# suicide-switch-circuit-with-usb-battery-.net
KiCad netlist of a schematic drawn in Altium Designer
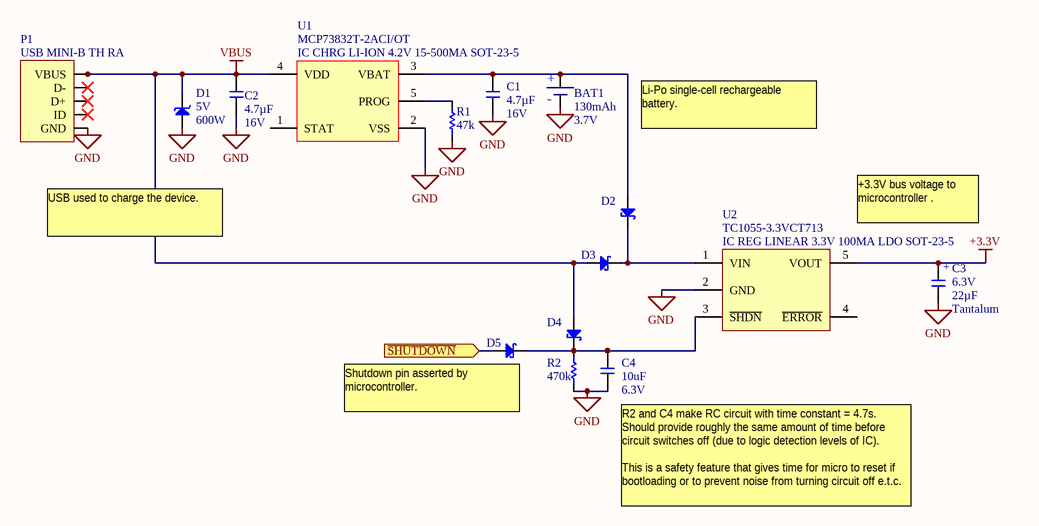
[diagram p0: suicide-switch-circuit-with-usb-battery-charger.SchDoc]

(export (version "E")
  (design (tool "Eeschema 10.0.6"))
  (components
    (comp (ref "BAT1")
      (value "BAT")
      (description "BATT LI-PO 1CELL")
      (fields (field (name "CAPACITY") "130mAh") (field (name "VOLTAGE") "3.7V"))
      (libsource (lib "Generic Components") (part "BATT"))
    )
    (comp (ref "C1")
      (value "EMK212BJ475KG-T")
      (footprint "Generic Footprints:CAP-N-1608[0603]")
      (description "CAP CER 4.7UF 16V 10% X5R 0805")
      (fields
        (field (name "MANUFACTURER") "Taiyo Yuden")
        (field (name "CAPACITANCE") "4.7µF")
        (field (name "VOLTAGE - RATED") "16V")
      )
      (libsource (lib "Specific Components") (part "EMK212BJ475KG-T"))
    )
    (comp (ref "C2")
      (value "EMK212BJ475KG-T")
      (footprint "Generic Footprints:CAP-N-1608[0603]")
      (description "CAP CER 4.7UF 16V 10% X5R 0805")
      (fields
        (field (name "MANUFACTURER") "Taiyo Yuden")
        (field (name "CAPACITANCE") "4.7µF")
        (field (name "VOLTAGE - RATED") "16V")
      )
      (libsource (lib "Specific Components") (part "EMK212BJ475KG-T"))
    )
    (comp (ref "C3")
      (value "TAJA226K006RNJ")
      (footprint "Generic Footprints:CAP TAN 3216[1206]")
      (description "CAP TANT 22UF 6.3V 10% 1206")
      (fields
        (field (name "MANUFACTURER") "AVX Corporation")
        (field (name "VOLTAGE - RATED") "6.3V")
        (field (name "CAPACITANCE") "22µF")
        (field (name "TYPE") "Tantalum")
      )
      (libsource (lib "Specific Components") (part "TAJA226K006RNJ"))
    )
    (comp (ref "C4")
      (value "GRM31CR60J107ME39L")
      (footprint "Generic Footprints:CAP-N-3216[1206]")
      (description "CAP CER 1206 100uF 6.3V X5R 20%")
      (fields (field (name "CAPACITANCE") "10uF") (field (name "VOLTAGE - RATED") "6.3V"))
      (libsource (lib "Specific Components") (part "GRM31CR60J107ME39L"))
    )
    (comp (ref "D1")
      (value "SMA6J5.0A-TR")
      (footprint "Generic Footprints:SMA (DO-214AC)")
      (description "TRANSIL 600W 5.0V UNIDIRECT SMA")
      (fields
        (field (name "MANUFACTURER") "STMicroelectronics")
        (field (name "VOLTAGE - REVERSE STANDOFF (TYP)") "5V")
        (field (name "POWER (WATTS)") "600W")
      )
      (libsource (lib "Specific Components") (part "SMA6J5.0A-TR"))
    )
    (comp (ref "D2")
      (value "CDBU0130L")
      (footprint "DIODE-N-1608[0603]")
      (description "DIODE SCHOTTKY 100MA 30V 0603")
      (fields (field (name "MANUFACTURER") "Comchip Technology"))
      (libsource (lib "Specific Components") (part "CDBU0130L"))
    )
    (comp (ref "D3")
      (value "CDBU0130L")
      (footprint "DIODE-N-1608[0603]")
      (description "DIODE SCHOTTKY 100MA 30V 0603")
      (fields (field (name "MANUFACTURER") "Comchip Technology"))
      (libsource (lib "Specific Components") (part "CDBU0130L"))
    )
    (comp (ref "D4")
      (value "CDBU0130L")
      (footprint "DIODE-N-1608[0603]")
      (description "DIODE SCHOTTKY 100MA 30V 0603")
      (fields (field (name "MANUFACTURER") "Comchip Technology"))
      (libsource (lib "Specific Components") (part "CDBU0130L"))
    )
    (comp (ref "D5")
      (value "CDBU0130L")
      (footprint "DIODE-N-1608[0603]")
      (description "DIODE SCHOTTKY 100MA 30V 0603")
      (fields (field (name "MANUFACTURER") "Comchip Technology"))
      (libsource (lib "Specific Components") (part "CDBU0130L"))
    )
    (comp (ref "P1")
      (value "USB MINI-B TH RA")
      (footprint "Connector Footprints:USB MINI-B TH RA")
      (description "USB MINI-B TH RA")
      (fields
        (field (name "MANUFACTURER") "Molex Inc")
        (field (name "MANUFACTURER PART NUMBER") "0548190519")
      )
      (libsource (lib "Connector Components") (part "USB MINI-B TH RA"))
    )
    (comp (ref "R1")
      (value "RC0603FR-0747KL")
      (footprint "Generic Footprints:RES-N-1608[0603]")
      (description "RES 47.0K OHM 1/10W 1% 0603 SMD")
      (fields (field (name "MANUFACTURER") "Yageo") (field (name "RESISTANCE (OHMS)") "47k"))
      (libsource (lib "Specific Components") (part "RC0603FR-0747KL"))
    )
    (comp (ref "R2")
      (value "RC0603FR-0747KL")
      (footprint "Generic Footprints:RES-N-1608[0603]")
      (description "RES 47.0K OHM 1/10W 1% 0603 SMD")
      (fields (field (name "MANUFACTURER") "Yageo") (field (name "RESISTANCE (OHMS)") "470k"))
      (libsource (lib "Specific Components") (part "RC0603FR-0747KL"))
    )
    (comp (ref "U1")
      (value "~")
      (footprint "Generic Footprints:SOT-23-5")
      (description "IC CHRG LI-ION 4.2V 15-500MA SOT-23-5")
      (fields
        (field (name "MANUFACTURER") "Microchip Technology")
        (field (name "MANUFACTURER PART NUMBER") "MCP73832T-2ACI/OT")
      )
      (libsource (lib "Specific Components") (part "MCP73832T-2ACI/OT"))
    )
    (comp (ref "U2")
      (value "TC1055-3.3VCT713")
      (footprint "Generic Footprints:SOT-23-5")
      (description "IC REG LINEAR 3.3V 100MA LDO SOT-23-5")
      (fields
        (field (name "MANUFACTURER") "Microchip Technology")
        (field (name "MANUFACTURER PART NUMBER") "TC1055-3.3VCT713")
      )
      (libsource (lib "Specific Components") (part "TC1055-3.3VCT713"))
    )
  )
  (nets
    (net (code "1") (name "+3.3V") (class "Default")
      (node (ref "C3") (pin "1") (pinfunction "1_1") (pintype "passive"))
      (node (ref "U2") (pin "5") (pinfunction "VOUT_5") (pintype "passive"))
    )
    (net (code "2") (name "/SHUTDOWN") (class "Default")
      (node (ref "D5") (pin "1") (pinfunction "A_1") (pintype "passive"))
    )
    (net (code "3") (name "GND") (class "Default")
      (node (ref "BAT1") (pin "2") (pinfunction "-_2") (pintype "passive"))
      (node (ref "C1") (pin "1") (pinfunction "1_1") (pintype "passive"))
      (node (ref "C2") (pin "1") (pinfunction "1_1") (pintype "passive"))
      (node (ref "C3") (pin "2") (pinfunction "2_2") (pintype "passive"))
      (node (ref "C4") (pin "1") (pinfunction "1_1") (pintype "passive"))
      (node (ref "D1") (pin "1") (pinfunction "A_1") (pintype "passive"))
      (node (ref "P1") (pin "5") (pinfunction "GND_5") (pintype "passive"))
      (node (ref "R1") (pin "1") (pinfunction "1_1") (pintype "passive"))
      (node (ref "R2") (pin "1") (pinfunction "1_1") (pintype "passive"))
      (node (ref "U1") (pin "2") (pinfunction "VSS_2") (pintype "passive"))
      (node (ref "U2") (pin "2") (pinfunction "GND_2") (pintype "passive"))
    )
    (net (code "4") (name "Net-(BAT1-+)") (class "Default")
      (node (ref "BAT1") (pin "1") (pinfunction "+_1") (pintype "passive"))
      (node (ref "C1") (pin "2") (pinfunction "2_2") (pintype "passive"))
      (node (ref "D2") (pin "1") (pinfunction "A_1") (pintype "passive"))
      (node (ref "U1") (pin "3") (pinfunction "VBAT_3") (pintype "passive"))
    )
    (net (code "5") (name "Net-(D2-K)") (class "Default")
      (node (ref "D2") (pin "2") (pinfunction "K_2") (pintype "passive"))
      (node (ref "D3") (pin "2") (pinfunction "K_2") (pintype "passive"))
      (node (ref "U2") (pin "1") (pinfunction "VIN_1") (pintype "passive"))
    )
    (net (code "6") (name "Net-(D4-K)") (class "Default")
      (node (ref "C4") (pin "2") (pinfunction "2_2") (pintype "passive"))
      (node (ref "D4") (pin "2") (pinfunction "K_2") (pintype "passive"))
      (node (ref "D5") (pin "2") (pinfunction "K_2") (pintype "passive"))
      (node (ref "R2") (pin "2") (pinfunction "2_2") (pintype "passive"))
      (node (ref "U2") (pin "3") (pinfunction "SHDN_3") (pintype "passive"))
    )
    (net (code "7") (name "Net-(U1-PROG)") (class "Default")
      (node (ref "R1") (pin "2") (pinfunction "2_2") (pintype "passive"))
      (node (ref "U1") (pin "5") (pinfunction "PROG_5") (pintype "passive"))
    )
    (net (code "8") (name "VBUS") (class "Default")
      (node (ref "C2") (pin "2") (pinfunction "2_2") (pintype "passive"))
      (node (ref "D1") (pin "2") (pinfunction "K_2") (pintype "passive"))
      (node (ref "D3") (pin "1") (pinfunction "A_1") (pintype "passive"))
      (node (ref "D4") (pin "1") (pinfunction "A_1") (pintype "passive"))
      (node (ref "P1") (pin "1") (pinfunction "VBUS_1") (pintype "passive"))
      (node (ref "U1") (pin "4") (pinfunction "VDD_4") (pintype "passive"))
    )
    (net (code "9") (name "unconnected-(P1-D+-Pad3)") (class "Default")
      (node (ref "P1") (pin "3") (pinfunction "D+_3") (pintype "passive+no_connect"))
    )
    (net (code "10") (name "unconnected-(P1-D--Pad2)") (class "Default")
      (node (ref "P1") (pin "2") (pinfunction "D-_2") (pintype "passive+no_connect"))
    )
    (net (code "11") (name "unconnected-(P1-ID-Pad4)") (class "Default")
      (node (ref "P1") (pin "4") (pinfunction "ID_4") (pintype "passive+no_connect"))
    )
    (net (code "12") (name "unconnected-(U1-STAT-Pad1)") (class "Default")
      (node (ref "U1") (pin "1") (pinfunction "STAT_1") (pintype "passive"))
    )
    (net (code "13") (name "unconnected-(U2-ERROR-Pad4)") (class "Default")
      (node (ref "U2") (pin "4") (pinfunction "ERROR_4") (pintype "passive"))
    )
  )
)
